# Smart_switch_edge_AI_V2.net
KiCad netlist of a schematic drawn in EAGLE
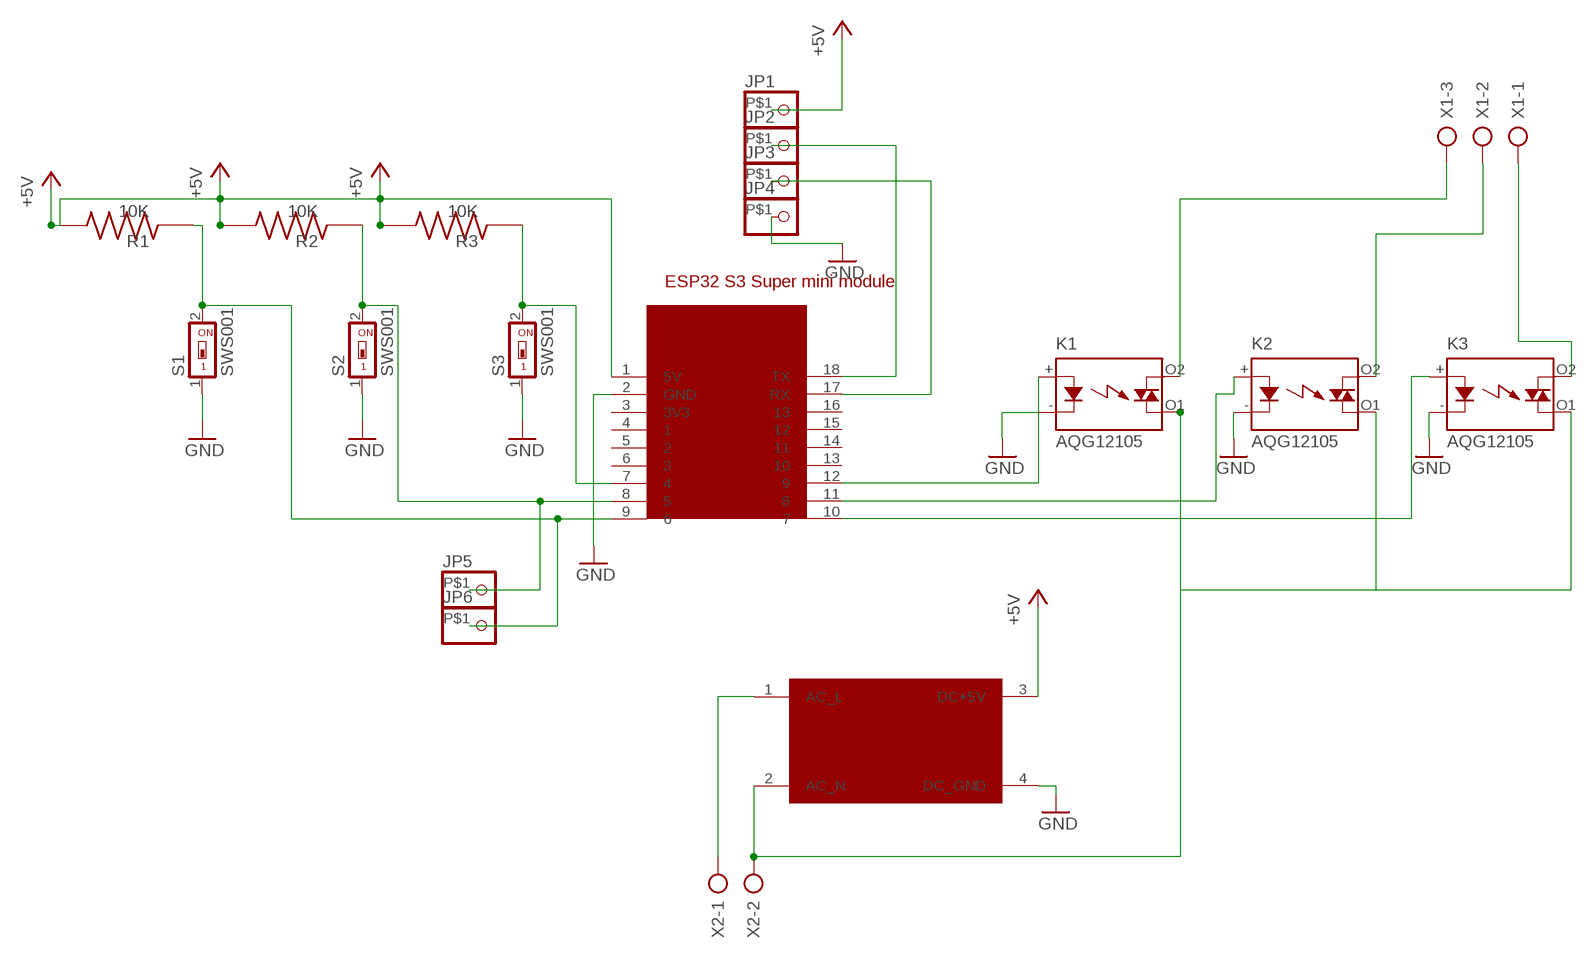
[diagram p0: schematic, sheet 1]

(export (version "E")
  (design (tool "Eeschema 10.0.6"))
  (components
    (comp (ref "JP1")
      (value "PINHD-1X1-BIGPOGO")
      (footprint "eagle-import:1X1-BIGPOGO")
      (libsource (lib "eagle-import") (part "PINHD-1X1-BIGPOGO"))
    )
    (comp (ref "JP2")
      (value "PINHD-1X1-BIGPOGO")
      (footprint "eagle-import:1X1-BIGPOGO")
      (libsource (lib "eagle-import") (part "PINHD-1X1-BIGPOGO"))
    )
    (comp (ref "JP3")
      (value "PINHD-1X1-BIGPOGO")
      (footprint "eagle-import:1X1-BIGPOGO")
      (libsource (lib "eagle-import") (part "PINHD-1X1-BIGPOGO"))
    )
    (comp (ref "JP4")
      (value "PINHD-1X1-BIGPOGO")
      (footprint "eagle-import:1X1-BIGPOGO")
      (libsource (lib "eagle-import") (part "PINHD-1X1-BIGPOGO"))
    )
    (comp (ref "JP5")
      (value "PINHD-1X1-BIGPOGO")
      (footprint "eagle-import:1X1-BIGPOGO")
      (libsource (lib "eagle-import") (part "PINHD-1X1-BIGPOGO"))
    )
    (comp (ref "JP6")
      (value "PINHD-1X1-BIGPOGO")
      (footprint "eagle-import:1X1-BIGPOGO")
      (libsource (lib "eagle-import") (part "PINHD-1X1-BIGPOGO"))
    )
    (comp (ref "K1")
      (value "AQG12105")
      (footprint "eagle-import:AQG")
      (fields (field (name "MF") "AROMAT/ MATSUSHITA"))
      (libsource (lib "eagle-import") (part "AQG12105"))
    )
    (comp (ref "K2")
      (value "AQG12105")
      (footprint "eagle-import:AQG")
      (fields (field (name "MF") "AROMAT/ MATSUSHITA"))
      (libsource (lib "eagle-import") (part "AQG12105"))
    )
    (comp (ref "K3")
      (value "AQG12105")
      (footprint "eagle-import:AQG")
      (fields (field (name "MF") "AROMAT/ MATSUSHITA"))
      (libsource (lib "eagle-import") (part "AQG12105"))
    )
    (comp (ref "R1")
      (value "10K")
      (footprint "eagle-import:RES_ERA6ARB512V")
      (fields (field (name "MF") "Panasonic") (field (name "MP") "ERA-6ARB512V"))
      (libsource (lib "eagle-import") (part "ERA6ARB512V"))
    )
    (comp (ref "R2")
      (value "10K")
      (footprint "eagle-import:RES_ERA6ARB512V")
      (fields (field (name "MF") "Panasonic") (field (name "MP") "ERA-6ARB512V"))
      (libsource (lib "eagle-import") (part "ERA6ARB512V"))
    )
    (comp (ref "R3")
      (value "10K")
      (footprint "eagle-import:RES_ERA6ARB512V")
      (fields (field (name "MF") "Panasonic") (field (name "MP") "ERA-6ARB512V"))
      (libsource (lib "eagle-import") (part "ERA6ARB512V"))
    )
    (comp (ref "S1")
      (value "SWS001")
      (footprint "eagle-import:SMS-001")
      (libsource (lib "eagle-import") (part "SWS001"))
    )
    (comp (ref "S2")
      (value "SWS001")
      (footprint "eagle-import:SMS-001")
      (libsource (lib "eagle-import") (part "SWS001"))
    )
    (comp (ref "S3")
      (value "SWS001")
      (footprint "eagle-import:SMS-001")
      (libsource (lib "eagle-import") (part "SWS001"))
    )
    (comp (ref "U$1")
      (value "ESP32_S3_SUPERMINI")
      (footprint "eagle-import:SON270P1795X2385X160-18N")
      (libsource (lib "eagle-import") (part "ESP32_S3_SUPERMINI"))
    )
    (comp (ref "U$2")
      (value "AL0505F")
      (footprint "eagle-import:DIP1650W60P600L1447H300Q4B")
      (libsource (lib "eagle-import") (part "AL0505F"))
    )
    (comp (ref "X1")
      (value "AK500/3")
      (footprint "eagle-import:AK500_3")
      (libsource (lib "eagle-import") (part "AK500/3"))
    )
    (comp (ref "X2")
      (value "AK500/2")
      (footprint "eagle-import:AK500_2")
      (libsource (lib "eagle-import") (part "AK500/2"))
    )
  )
  (nets
    (net (code "1") (name "+5V") (class "Default")
      (node (ref "JP1") (pin "P$1") (pinfunction "1_P$1") (pintype "passive"))
      (node (ref "R1") (pin "2") (pinfunction "2_2") (pintype "passive"))
      (node (ref "R2") (pin "2") (pinfunction "2_2") (pintype "passive"))
      (node (ref "R3") (pin "2") (pinfunction "2_2") (pintype "passive"))
      (node (ref "U$1") (pin "1") (pinfunction "5V_1") (pintype "bidirectional"))
      (node (ref "U$2") (pin "3") (pinfunction "DC+5V_3") (pintype "bidirectional"))
    )
    (net (code "2") (name "GND") (class "Default")
      (node (ref "JP4") (pin "P$1") (pinfunction "1_P$1") (pintype "passive"))
      (node (ref "K1") (pin "-") (pinfunction "K_-") (pintype "passive"))
      (node (ref "K2") (pin "-") (pinfunction "K_-") (pintype "passive"))
      (node (ref "K3") (pin "-") (pinfunction "K_-") (pintype "passive"))
      (node (ref "S1") (pin "1") (pinfunction "1_1") (pintype "passive"))
      (node (ref "S2") (pin "1") (pinfunction "1_1") (pintype "passive"))
      (node (ref "S3") (pin "1") (pinfunction "1_1") (pintype "passive"))
      (node (ref "U$1") (pin "2") (pinfunction "GND_2") (pintype "bidirectional"))
      (node (ref "U$2") (pin "4") (pinfunction "DC_GND_4") (pintype "bidirectional"))
    )
    (net (code "3") (name "Net-(JP2-1)") (class "Default")
      (node (ref "JP2") (pin "P$1") (pinfunction "1_P$1") (pintype "passive"))
      (node (ref "U$1") (pin "18") (pinfunction "TX_18") (pintype "bidirectional"))
    )
    (net (code "4") (name "Net-(JP3-1)") (class "Default")
      (node (ref "JP3") (pin "P$1") (pinfunction "1_P$1") (pintype "passive"))
      (node (ref "U$1") (pin "17") (pinfunction "RX_17") (pintype "bidirectional"))
    )
    (net (code "5") (name "Net-(JP5-1)") (class "Default")
      (node (ref "JP5") (pin "P$1") (pinfunction "1_P$1") (pintype "passive"))
      (node (ref "R2") (pin "1") (pinfunction "1_1") (pintype "passive"))
      (node (ref "S2") (pin "2") (pinfunction "2_2") (pintype "passive"))
      (node (ref "U$1") (pin "8") (pinfunction "5_8") (pintype "bidirectional"))
    )
    (net (code "6") (name "Net-(JP6-1)") (class "Default")
      (node (ref "JP6") (pin "P$1") (pinfunction "1_P$1") (pintype "passive"))
      (node (ref "R1") (pin "1") (pinfunction "1_1") (pintype "passive"))
      (node (ref "S1") (pin "2") (pinfunction "2_2") (pintype "passive"))
      (node (ref "U$1") (pin "9") (pinfunction "6_9") (pintype "bidirectional"))
    )
    (net (code "7") (name "Net-(K1-A)") (class "Default")
      (node (ref "K1") (pin "+") (pinfunction "A_+") (pintype "passive"))
      (node (ref "U$1") (pin "12") (pinfunction "9_12") (pintype "bidirectional"))
    )
    (net (code "8") (name "Net-(K1-DS1)") (class "Default")
      (node (ref "K1") (pin "O2") (pinfunction "DS1_O2") (pintype "passive"))
      (node (ref "X1") (pin "3") (pinfunction "KL_3") (pintype "passive"))
    )
    (net (code "9") (name "Net-(K1-DS2)") (class "Default")
      (node (ref "K1") (pin "O1") (pinfunction "DS2_O1") (pintype "passive"))
      (node (ref "K2") (pin "O1") (pinfunction "DS2_O1") (pintype "passive"))
      (node (ref "K3") (pin "O1") (pinfunction "DS2_O1") (pintype "passive"))
      (node (ref "U$2") (pin "2") (pinfunction "AC_N_2") (pintype "bidirectional"))
      (node (ref "X2") (pin "2") (pinfunction "KL_2") (pintype "passive"))
    )
    (net (code "10") (name "Net-(K2-A)") (class "Default")
      (node (ref "K2") (pin "+") (pinfunction "A_+") (pintype "passive"))
      (node (ref "U$1") (pin "11") (pinfunction "8_11") (pintype "bidirectional"))
    )
    (net (code "11") (name "Net-(K2-DS1)") (class "Default")
      (node (ref "K2") (pin "O2") (pinfunction "DS1_O2") (pintype "passive"))
      (node (ref "X1") (pin "2") (pinfunction "KL_2") (pintype "passive"))
    )
    (net (code "12") (name "Net-(K3-A)") (class "Default")
      (node (ref "K3") (pin "+") (pinfunction "A_+") (pintype "passive"))
      (node (ref "U$1") (pin "10") (pinfunction "7_10") (pintype "bidirectional"))
    )
    (net (code "13") (name "Net-(K3-DS1)") (class "Default")
      (node (ref "K3") (pin "O2") (pinfunction "DS1_O2") (pintype "passive"))
      (node (ref "X1") (pin "1") (pinfunction "KL_1") (pintype "passive"))
    )
    (net (code "14") (name "Net-(U$1-4)") (class "Default")
      (node (ref "R3") (pin "1") (pinfunction "1_1") (pintype "passive"))
      (node (ref "S3") (pin "2") (pinfunction "2_2") (pintype "passive"))
      (node (ref "U$1") (pin "7") (pinfunction "4_7") (pintype "bidirectional"))
    )
    (net (code "15") (name "Net-(U$2-AC_L)") (class "Default")
      (node (ref "U$2") (pin "1") (pinfunction "AC_L_1") (pintype "bidirectional"))
      (node (ref "X2") (pin "1") (pinfunction "KL_1") (pintype "passive"))
    )
    (net (code "16") (name "unconnected-(U$1-1-Pad4)") (class "Default")
      (node (ref "U$1") (pin "4") (pinfunction "1_4") (pintype "bidirectional"))
    )
    (net (code "17") (name "unconnected-(U$1-2-Pad5)") (class "Default")
      (node (ref "U$1") (pin "5") (pinfunction "2_5") (pintype "bidirectional"))
    )
    (net (code "18") (name "unconnected-(U$1-3-Pad6)") (class "Default")
      (node (ref "U$1") (pin "6") (pinfunction "3_6") (pintype "bidirectional"))
    )
    (net (code "19") (name "unconnected-(U$1-3V3-Pad3)") (class "Default")
      (node (ref "U$1") (pin "3") (pinfunction "3V3_3") (pintype "bidirectional"))
    )
    (net (code "20") (name "unconnected-(U$1-10-Pad13)") (class "Default")
      (node (ref "U$1") (pin "13") (pinfunction "10_13") (pintype "bidirectional"))
    )
    (net (code "21") (name "unconnected-(U$1-11-Pad14)") (class "Default")
      (node (ref "U$1") (pin "14") (pinfunction "11_14") (pintype "bidirectional"))
    )
    (net (code "22") (name "unconnected-(U$1-12-Pad15)") (class "Default")
      (node (ref "U$1") (pin "15") (pinfunction "12_15") (pintype "bidirectional"))
    )
    (net (code "23") (name "unconnected-(U$1-13-Pad16)") (class "Default")
      (node (ref "U$1") (pin "16") (pinfunction "13_16") (pintype "bidirectional"))
    )
  )
)
